# Main_Board.net
KiCad netlist of a schematic drawn in EAGLE
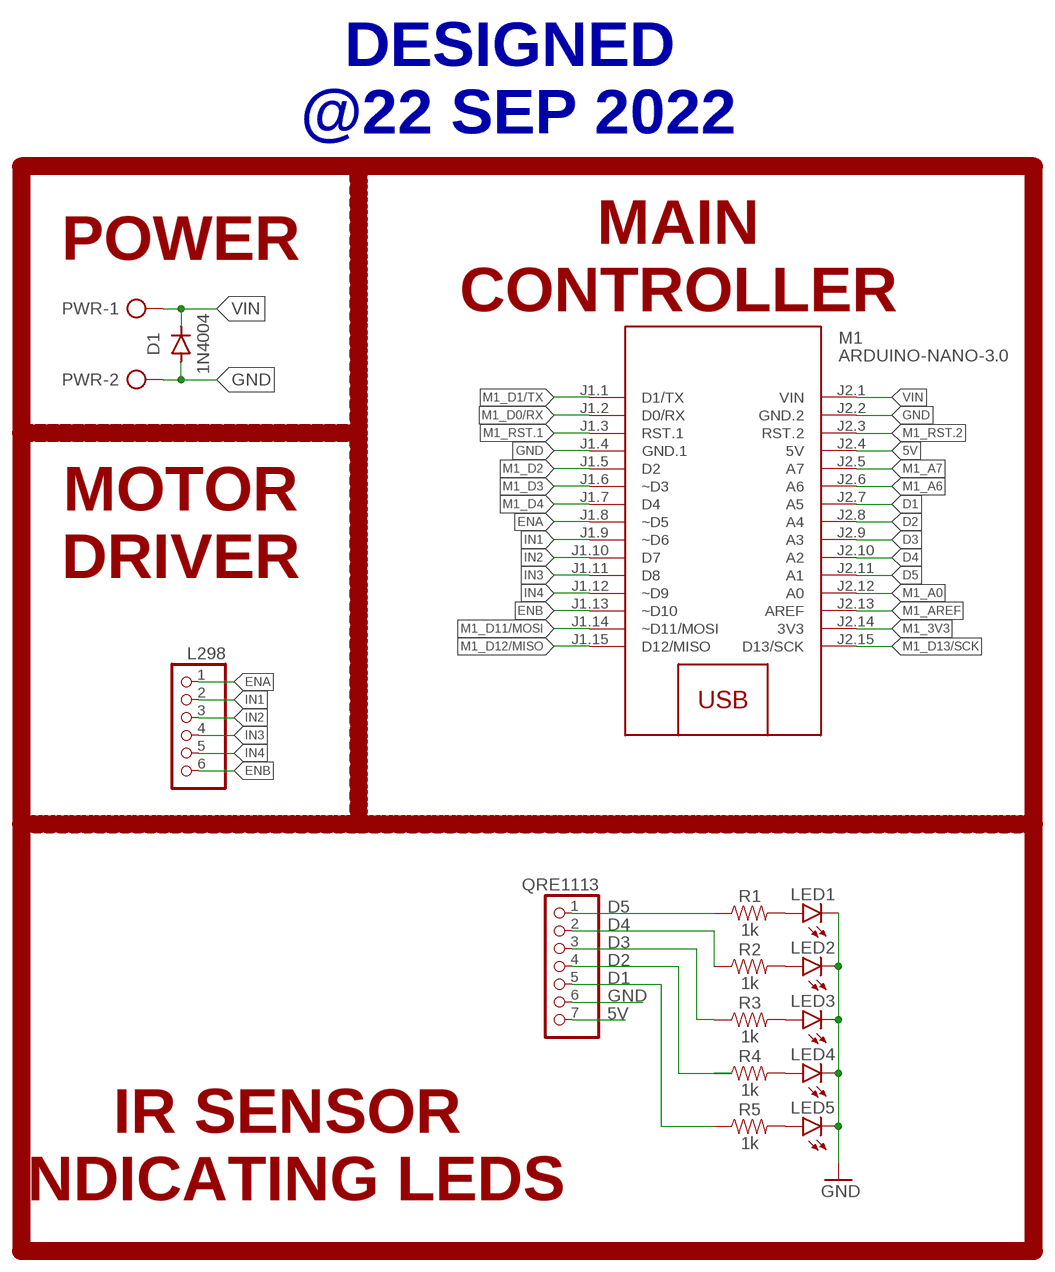
[diagram p0: schematic, sheet 1]

(export (version "E")
  (design (tool "Eeschema 10.0.6"))
  (components
    (comp (ref "D1")
      (value "1N4004")
      (footprint "eagle-import:DO41-10")
      (libsource (lib "eagle-import") (part "1N4004"))
    )
    (comp (ref "L298")
      (value "PINHD-1X6")
      (footprint "eagle-import:1X06")
      (libsource (lib "eagle-import") (part "PINHD-1X6"))
    )
    (comp (ref "LED1")
      (value "LED5MM")
      (footprint "eagle-import:LED5MM")
      (libsource (lib "eagle-import") (part "LED5MM"))
    )
    (comp (ref "LED2")
      (value "LED5MM")
      (footprint "eagle-import:LED5MM")
      (libsource (lib "eagle-import") (part "LED5MM"))
    )
    (comp (ref "LED3")
      (value "LED5MM")
      (footprint "eagle-import:LED5MM")
      (libsource (lib "eagle-import") (part "LED5MM"))
    )
    (comp (ref "LED4")
      (value "LED5MM")
      (footprint "eagle-import:LED5MM")
      (libsource (lib "eagle-import") (part "LED5MM"))
    )
    (comp (ref "LED5")
      (value "LED5MM")
      (footprint "eagle-import:LED5MM")
      (libsource (lib "eagle-import") (part "LED5MM"))
    )
    (comp (ref "M1")
      (value "ARDUINO-NANO-3.0")
      (footprint "eagle-import:ARDUINO-NANO-3.0")
      (libsource (lib "eagle-import") (part "ARDUINO-NANO-3.0"))
    )
    (comp (ref "PWR") (value "2P") (footprint "eagle-import:2P") (libsource (lib "eagle-import") (part "2P")))
    (comp (ref "QRE1113")
      (value "PINHD-1X7/90")
      (footprint "eagle-import:1X07_90")
      (libsource (lib "eagle-import") (part "PINHD-1X7/90"))
    )
    (comp (ref "R1")
      (value "1k")
      (footprint "eagle-import:AXIAL-0.3")
      (libsource (lib "eagle-import") (part "RESISTORAXIAL-0.3"))
    )
    (comp (ref "R2")
      (value "1k")
      (footprint "eagle-import:AXIAL-0.3")
      (libsource (lib "eagle-import") (part "RESISTORAXIAL-0.3"))
    )
    (comp (ref "R3")
      (value "1k")
      (footprint "eagle-import:AXIAL-0.3")
      (libsource (lib "eagle-import") (part "RESISTORAXIAL-0.3"))
    )
    (comp (ref "R4")
      (value "1k")
      (footprint "eagle-import:AXIAL-0.3")
      (libsource (lib "eagle-import") (part "RESISTORAXIAL-0.3"))
    )
    (comp (ref "R5")
      (value "1k")
      (footprint "eagle-import:AXIAL-0.3")
      (libsource (lib "eagle-import") (part "RESISTORAXIAL-0.3"))
    )
  )
  (nets
    (net (code "1") (name "5V") (class "Default")
      (node (ref "M1") (pin "J2.4") (pinfunction "5V_J2.4") (pintype "power_in"))
      (node (ref "QRE1113") (pin "7") (pinfunction "7_7") (pintype "passive"))
    )
    (net (code "2") (name "D1") (class "Default")
      (node (ref "M1") (pin "J2.7") (pinfunction "A5_J2.7") (pintype "bidirectional"))
      (node (ref "QRE1113") (pin "5") (pinfunction "5_5") (pintype "passive"))
      (node (ref "R5") (pin "P$1") (pinfunction "1_P$1") (pintype "passive"))
    )
    (net (code "3") (name "D2") (class "Default")
      (node (ref "M1") (pin "J2.8") (pinfunction "A4_J2.8") (pintype "bidirectional"))
      (node (ref "QRE1113") (pin "4") (pinfunction "4_4") (pintype "passive"))
      (node (ref "R4") (pin "P$1") (pinfunction "1_P$1") (pintype "passive"))
    )
    (net (code "4") (name "D3") (class "Default")
      (node (ref "M1") (pin "J2.9") (pinfunction "A3_J2.9") (pintype "bidirectional"))
      (node (ref "QRE1113") (pin "3") (pinfunction "3_3") (pintype "passive"))
      (node (ref "R3") (pin "P$1") (pinfunction "1_P$1") (pintype "passive"))
    )
    (net (code "5") (name "D4") (class "Default")
      (node (ref "M1") (pin "J2.10") (pinfunction "A2_J2.10") (pintype "bidirectional"))
      (node (ref "QRE1113") (pin "2") (pinfunction "2_2") (pintype "passive"))
      (node (ref "R2") (pin "P$1") (pinfunction "1_P$1") (pintype "passive"))
    )
    (net (code "6") (name "D5") (class "Default")
      (node (ref "M1") (pin "J2.11") (pinfunction "A1_J2.11") (pintype "bidirectional"))
      (node (ref "QRE1113") (pin "1") (pinfunction "1_1") (pintype "passive"))
      (node (ref "R1") (pin "P$1") (pinfunction "1_P$1") (pintype "passive"))
    )
    (net (code "7") (name "ENA") (class "Default")
      (node (ref "L298") (pin "1") (pinfunction "1_1") (pintype "passive"))
      (node (ref "M1") (pin "J1.8") (pinfunction "~{D5}_J1.8") (pintype "bidirectional"))
    )
    (net (code "8") (name "ENB") (class "Default")
      (node (ref "L298") (pin "6") (pinfunction "6_6") (pintype "passive"))
      (node (ref "M1") (pin "J1.13") (pinfunction "~{D10}_J1.13") (pintype "bidirectional"))
    )
    (net (code "9") (name "GND") (class "Default")
      (node (ref "D1") (pin "A") (pinfunction "A_A") (pintype "passive"))
      (node (ref "LED1") (pin "K") (pinfunction "C_K") (pintype "passive"))
      (node (ref "LED2") (pin "K") (pinfunction "C_K") (pintype "passive"))
      (node (ref "LED3") (pin "K") (pinfunction "C_K") (pintype "passive"))
      (node (ref "LED4") (pin "K") (pinfunction "C_K") (pintype "passive"))
      (node (ref "LED5") (pin "K") (pinfunction "C_K") (pintype "passive"))
      (node (ref "M1") (pin "J1.4") (pinfunction "GND.1_J1.4") (pintype "power_in"))
      (node (ref "M1") (pin "J2.2") (pinfunction "GND.2_J2.2") (pintype "power_in"))
      (node (ref "PWR") (pin "2") (pinfunction "KL_2") (pintype "passive"))
      (node (ref "QRE1113") (pin "6") (pinfunction "6_6") (pintype "passive"))
    )
    (net (code "10") (name "IN1") (class "Default")
      (node (ref "L298") (pin "2") (pinfunction "2_2") (pintype "passive"))
      (node (ref "M1") (pin "J1.9") (pinfunction "~{D6}_J1.9") (pintype "bidirectional"))
    )
    (net (code "11") (name "IN2") (class "Default")
      (node (ref "L298") (pin "3") (pinfunction "3_3") (pintype "passive"))
      (node (ref "M1") (pin "J1.10") (pinfunction "D7_J1.10") (pintype "bidirectional"))
    )
    (net (code "12") (name "IN3") (class "Default")
      (node (ref "L298") (pin "4") (pinfunction "4_4") (pintype "passive"))
      (node (ref "M1") (pin "J1.11") (pinfunction "D8_J1.11") (pintype "bidirectional"))
    )
    (net (code "13") (name "IN4") (class "Default")
      (node (ref "L298") (pin "5") (pinfunction "5_5") (pintype "passive"))
      (node (ref "M1") (pin "J1.12") (pinfunction "~{D9}_J1.12") (pintype "bidirectional"))
    )
    (net (code "14") (name "M1_3V3") (class "Default")
      (node (ref "M1") (pin "J2.14") (pinfunction "3V3_J2.14") (pintype "power_in"))
    )
    (net (code "15") (name "M1_A0") (class "Default")
      (node (ref "M1") (pin "J2.12") (pinfunction "A0_J2.12") (pintype "bidirectional"))
    )
    (net (code "16") (name "M1_A6") (class "Default")
      (node (ref "M1") (pin "J2.6") (pinfunction "A6_J2.6") (pintype "bidirectional"))
    )
    (net (code "17") (name "M1_A7") (class "Default")
      (node (ref "M1") (pin "J2.5") (pinfunction "A7_J2.5") (pintype "bidirectional"))
    )
    (net (code "18") (name "M1_AREF") (class "Default")
      (node (ref "M1") (pin "J2.13") (pinfunction "AREF_J2.13") (pintype "bidirectional"))
    )
    (net (code "19") (name "M1_D0{slash}RX") (class "Default")
      (node (ref "M1") (pin "J1.2") (pinfunction "D0/RX_J1.2") (pintype "bidirectional"))
    )
    (net (code "20") (name "M1_D1{slash}TX") (class "Default")
      (node (ref "M1") (pin "J1.1") (pinfunction "D1/TX_J1.1") (pintype "bidirectional"))
    )
    (net (code "21") (name "M1_D2") (class "Default")
      (node (ref "M1") (pin "J1.5") (pinfunction "D2_J1.5") (pintype "bidirectional"))
    )
    (net (code "22") (name "M1_D3") (class "Default")
      (node (ref "M1") (pin "J1.6") (pinfunction "~{D3}_J1.6") (pintype "bidirectional"))
    )
    (net (code "23") (name "M1_D4") (class "Default")
      (node (ref "M1") (pin "J1.7") (pinfunction "D4_J1.7") (pintype "bidirectional"))
    )
    (net (code "24") (name "M1_D11{slash}MOSI") (class "Default")
      (node (ref "M1") (pin "J1.14") (pinfunction "~{D11/MOSI}_J1.14") (pintype "bidirectional"))
    )
    (net (code "25") (name "M1_D12{slash}MISO") (class "Default")
      (node (ref "M1") (pin "J1.15") (pinfunction "D12/MISO_J1.15") (pintype "bidirectional"))
    )
    (net (code "26") (name "M1_D13{slash}SCK") (class "Default")
      (node (ref "M1") (pin "J2.15") (pinfunction "D13/SCK_J2.15") (pintype "bidirectional"))
    )
    (net (code "27") (name "M1_RST.1") (class "Default")
      (node (ref "M1") (pin "J1.3") (pinfunction "RST.1_J1.3") (pintype "bidirectional"))
    )
    (net (code "28") (name "M1_RST.2") (class "Default")
      (node (ref "M1") (pin "J2.3") (pinfunction "RST.2_J2.3") (pintype "bidirectional"))
    )
    (net (code "29") (name "Net-(R1-2)") (class "Default")
      (node (ref "LED1") (pin "A") (pinfunction "A_A") (pintype "passive"))
      (node (ref "R1") (pin "P$2") (pinfunction "2_P$2") (pintype "passive"))
    )
    (net (code "30") (name "Net-(R2-2)") (class "Default")
      (node (ref "LED2") (pin "A") (pinfunction "A_A") (pintype "passive"))
      (node (ref "R2") (pin "P$2") (pinfunction "2_P$2") (pintype "passive"))
    )
    (net (code "31") (name "Net-(R3-2)") (class "Default")
      (node (ref "LED3") (pin "A") (pinfunction "A_A") (pintype "passive"))
      (node (ref "R3") (pin "P$2") (pinfunction "2_P$2") (pintype "passive"))
    )
    (net (code "32") (name "Net-(R4-2)") (class "Default")
      (node (ref "LED4") (pin "A") (pinfunction "A_A") (pintype "passive"))
      (node (ref "R4") (pin "P$2") (pinfunction "2_P$2") (pintype "passive"))
    )
    (net (code "33") (name "Net-(R5-2)") (class "Default")
      (node (ref "LED5") (pin "A") (pinfunction "A_A") (pintype "passive"))
      (node (ref "R5") (pin "P$2") (pinfunction "2_P$2") (pintype "passive"))
    )
    (net (code "34") (name "VIN") (class "Default")
      (node (ref "D1") (pin "C") (pinfunction "C_C") (pintype "passive"))
      (node (ref "M1") (pin "J2.1") (pinfunction "VIN_J2.1") (pintype "power_in"))
      (node (ref "PWR") (pin "1") (pinfunction "KL_1") (pintype "passive"))
    )
  )
)
